# 1dpong.net
KiCad netlist of a schematic drawn in EAGLE
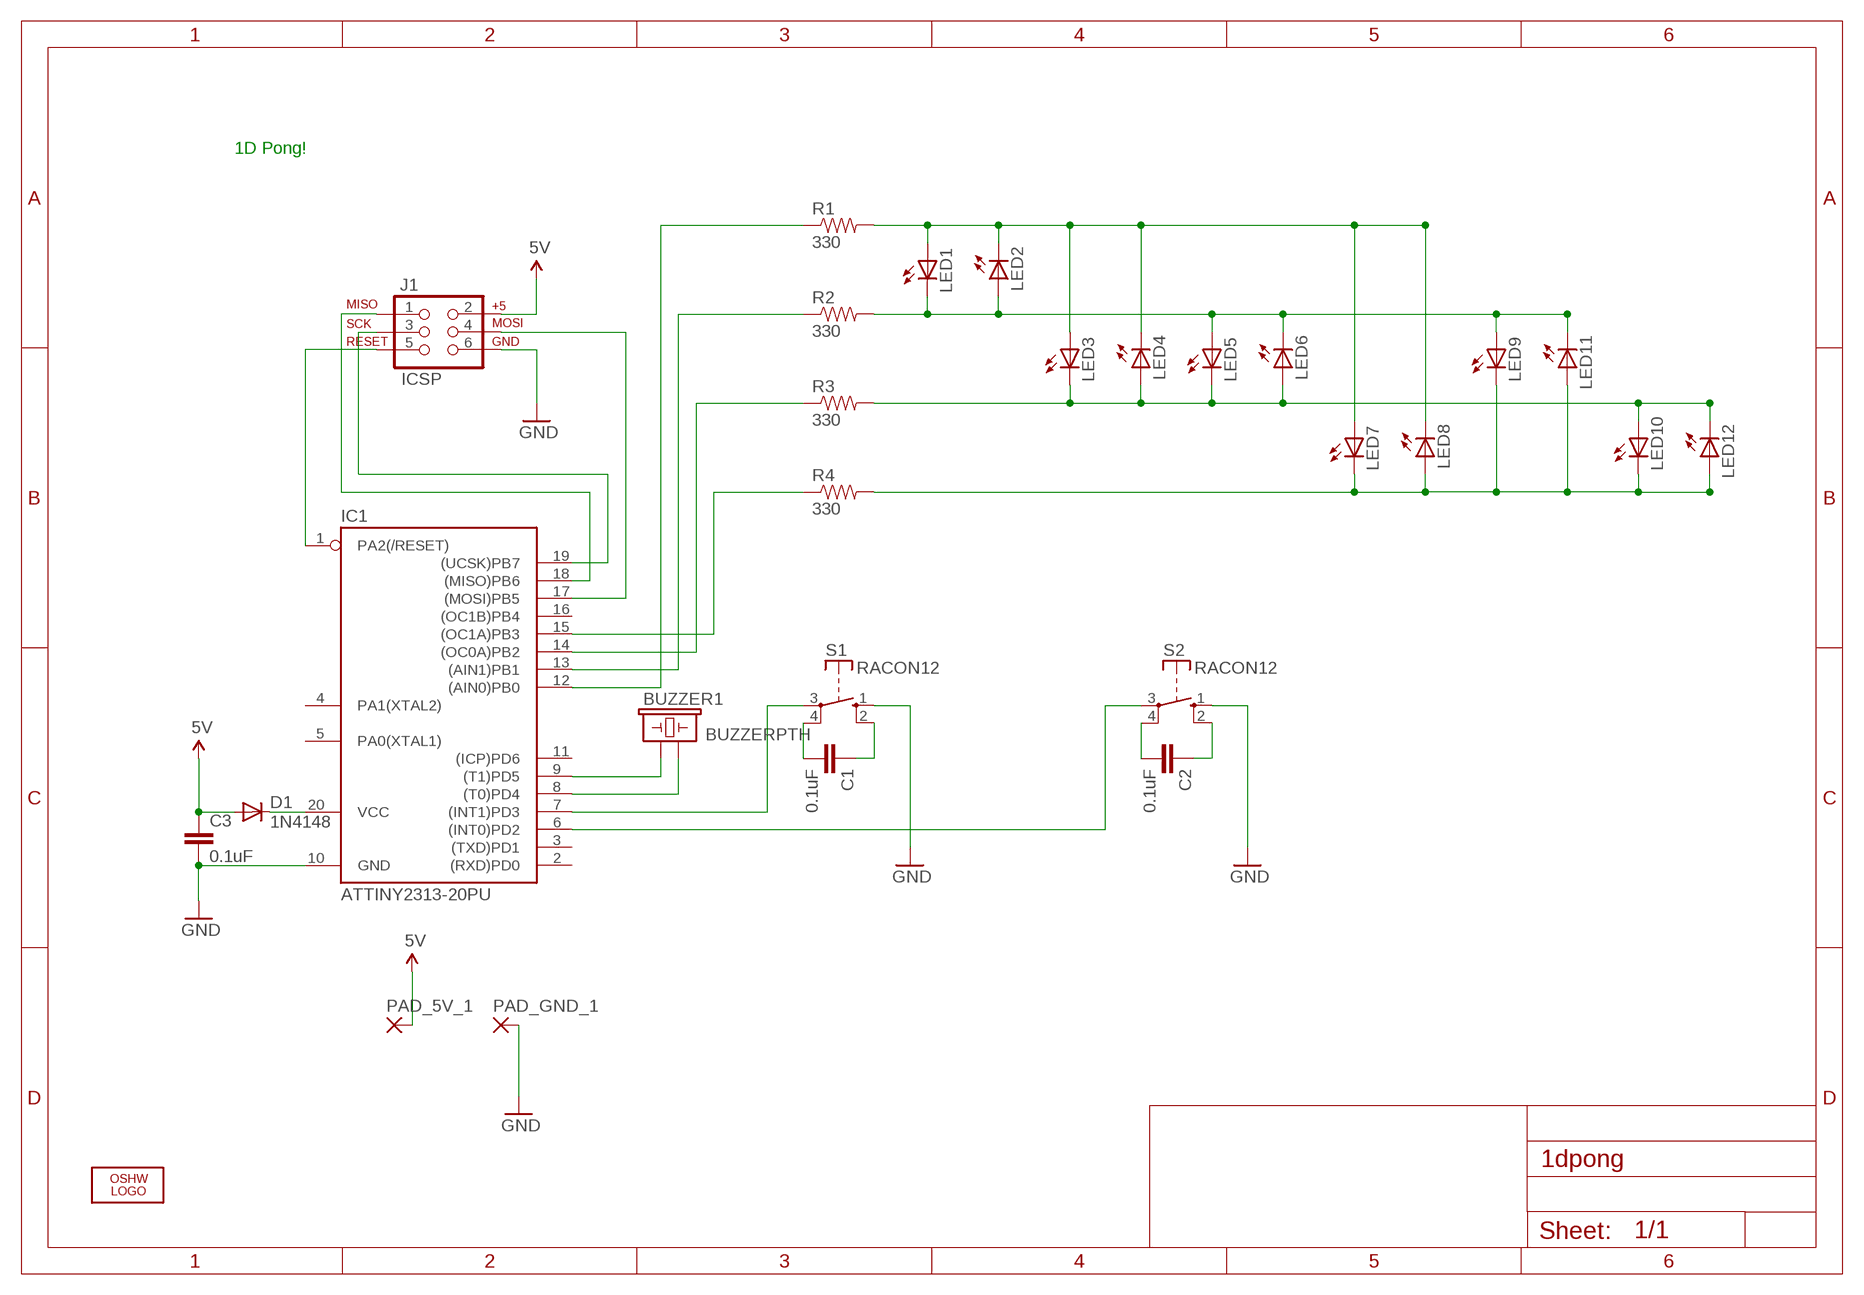
[diagram p0: schematic, sheet 1]

(export (version "E")
  (design (tool "Eeschema 10.0.6"))
  (components
    (comp (ref "BUZZER1")
      (value "BUZZERPTH")
      (footprint "eagle-import:BUZZER-12MM")
      (libsource (lib "eagle-import") (part "BUZZERPTH"))
    )
    (comp (ref "C1")
      (value "0.1uF")
      (footprint "eagle-import:CAP-PTH-SMALL")
      (libsource (lib "eagle-import") (part "CAPPTH"))
    )
    (comp (ref "C2")
      (value "0.1uF")
      (footprint "eagle-import:CAP-PTH-SMALL")
      (libsource (lib "eagle-import") (part "CAPPTH"))
    )
    (comp (ref "C3")
      (value "0.1uF")
      (footprint "eagle-import:CAP-PTH-SMALL")
      (libsource (lib "eagle-import") (part "CAPPTH"))
    )
    (comp (ref "D1")
      (value "1N4148")
      (footprint "eagle-import:DIODE-1N4148")
      (libsource (lib "eagle-import") (part "DIODE1N4148"))
    )
    (comp (ref "IC1")
      (value "ATTINY2313-20PU")
      (footprint "eagle-import:DIL20")
      (libsource (lib "eagle-import") (part "TINY2313-P"))
    )
    (comp (ref "J1")
      (value "ICSP")
      (footprint "eagle-import:2X3")
      (libsource (lib "eagle-import") (part "AVR_SPI_PRG_6PTH"))
    )
    (comp (ref "LED1")
      (value "LED5MM")
      (footprint "eagle-import:LED5MM")
      (libsource (lib "eagle-import") (part "LED5MM"))
    )
    (comp (ref "LED2")
      (value "LED5MM")
      (footprint "eagle-import:LED5MM")
      (libsource (lib "eagle-import") (part "LED5MM"))
    )
    (comp (ref "LED3")
      (value "LED5MM")
      (footprint "eagle-import:LED5MM")
      (libsource (lib "eagle-import") (part "LED5MM"))
    )
    (comp (ref "LED4")
      (value "LED5MM")
      (footprint "eagle-import:LED5MM")
      (libsource (lib "eagle-import") (part "LED5MM"))
    )
    (comp (ref "LED5")
      (value "LED5MM")
      (footprint "eagle-import:LED5MM")
      (libsource (lib "eagle-import") (part "LED5MM"))
    )
    (comp (ref "LED6")
      (value "LED5MM")
      (footprint "eagle-import:LED5MM")
      (libsource (lib "eagle-import") (part "LED5MM"))
    )
    (comp (ref "LED7")
      (value "LED5MM")
      (footprint "eagle-import:LED5MM")
      (libsource (lib "eagle-import") (part "LED5MM"))
    )
    (comp (ref "LED8")
      (value "LED5MM")
      (footprint "eagle-import:LED5MM")
      (libsource (lib "eagle-import") (part "LED5MM"))
    )
    (comp (ref "LED9")
      (value "LED5MM")
      (footprint "eagle-import:LED5MM")
      (libsource (lib "eagle-import") (part "LED5MM"))
    )
    (comp (ref "LED10")
      (value "LED5MM")
      (footprint "eagle-import:LED5MM")
      (libsource (lib "eagle-import") (part "LED5MM"))
    )
    (comp (ref "LED11")
      (value "LED5MM")
      (footprint "eagle-import:LED5MM")
      (libsource (lib "eagle-import") (part "LED5MM"))
    )
    (comp (ref "LED12")
      (value "LED5MM")
      (footprint "eagle-import:LED5MM")
      (libsource (lib "eagle-import") (part "LED5MM"))
    )
    (comp (ref "LOGO1")
      (value "OSHW_LOGO_FILLX0150-NT")
      (footprint "eagle-import:OSHW_FILLX150_NOTEXT")
      (libsource (lib "eagle-import") (part "OSHW_LOGO_FILLX0150-NT"))
    )
    (comp (ref "PAD_5V_1")
      (value "WIREPAD1,6/0,9")
      (footprint "eagle-import:1,6_0,9")
      (libsource (lib "eagle-import") (part "WIREPAD1,6/0,9"))
    )
    (comp (ref "PAD_GND_1")
      (value "WIREPAD1,6/0,9")
      (footprint "eagle-import:1,6_0,9")
      (libsource (lib "eagle-import") (part "WIREPAD1,6/0,9"))
    )
    (comp (ref "R1")
      (value "330")
      (footprint "eagle-import:AXIAL-0.4")
      (libsource (lib "eagle-import") (part "RESISTORPTH-1/4W"))
    )
    (comp (ref "R2")
      (value "330")
      (footprint "eagle-import:AXIAL-0.4")
      (libsource (lib "eagle-import") (part "RESISTORPTH-1/4W"))
    )
    (comp (ref "R3")
      (value "330")
      (footprint "eagle-import:AXIAL-0.4")
      (libsource (lib "eagle-import") (part "RESISTORPTH-1/4W"))
    )
    (comp (ref "R4")
      (value "330")
      (footprint "eagle-import:AXIAL-0.4")
      (libsource (lib "eagle-import") (part "RESISTORPTH-1/4W"))
    )
    (comp (ref "S1")
      (value "RACON12")
      (footprint "eagle-import:RACON12")
      (libsource (lib "eagle-import") (part "RACON12"))
    )
    (comp (ref "S2")
      (value "RACON12")
      (footprint "eagle-import:RACON12")
      (libsource (lib "eagle-import") (part "RACON12"))
    )
  )
  (nets
    (net (code "1") (name "5V") (class "Default")
      (node (ref "C3") (pin "1") (pinfunction "1_1") (pintype "passive"))
      (node (ref "D1") (pin "A") (pinfunction "A_A") (pintype "passive"))
      (node (ref "J1") (pin "2") (pinfunction "2_2") (pintype "passive"))
      (node (ref "PAD_5V_1") (pin "1") (pinfunction "P_1") (pintype "passive"))
    )
    (net (code "2") (name "GND") (class "Default")
      (node (ref "C3") (pin "2") (pinfunction "2_2") (pintype "passive"))
      (node (ref "IC1") (pin "10") (pinfunction "GND_10") (pintype "power_in"))
      (node (ref "J1") (pin "6") (pinfunction "6_6") (pintype "passive"))
      (node (ref "PAD_GND_1") (pin "1") (pinfunction "P_1") (pintype "passive"))
      (node (ref "S1") (pin "1") (pinfunction "S_1") (pintype "passive"))
      (node (ref "S2") (pin "1") (pinfunction "S_1") (pintype "passive"))
    )
    (net (code "3") (name "Net-(BUZZER1-1)") (class "Default")
      (node (ref "BUZZER1") (pin "+") (pinfunction "1_+") (pintype "passive"))
      (node (ref "IC1") (pin "9") (pinfunction "(T1)PD5_9") (pintype "bidirectional"))
    )
    (net (code "4") (name "Net-(BUZZER1-2)") (class "Default")
      (node (ref "BUZZER1") (pin "-") (pinfunction "2_-") (pintype "passive"))
      (node (ref "IC1") (pin "8") (pinfunction "(T0)PD4_8") (pintype "bidirectional"))
    )
    (net (code "5") (name "Net-(C1-Pad1)") (class "Default")
      (node (ref "C1") (pin "1") (pinfunction "1_1") (pintype "passive"))
      (node (ref "S1") (pin "2") (pinfunction "S_2") (pintype "passive"))
    )
    (net (code "6") (name "Net-(C1-Pad2)") (class "Default")
      (node (ref "C1") (pin "2") (pinfunction "2_2") (pintype "passive"))
      (node (ref "S1") (pin "4") (pinfunction "P_4") (pintype "passive"))
    )
    (net (code "7") (name "Net-(C2-Pad1)") (class "Default")
      (node (ref "C2") (pin "1") (pinfunction "1_1") (pintype "passive"))
      (node (ref "S2") (pin "2") (pinfunction "S_2") (pintype "passive"))
    )
    (net (code "8") (name "Net-(C2-Pad2)") (class "Default")
      (node (ref "C2") (pin "2") (pinfunction "2_2") (pintype "passive"))
      (node (ref "S2") (pin "4") (pinfunction "P_4") (pintype "passive"))
    )
    (net (code "9") (name "Net-(IC1-(AIN0)PB0)") (class "Default")
      (node (ref "IC1") (pin "12") (pinfunction "(AIN0)PB0_12") (pintype "bidirectional"))
      (node (ref "R1") (pin "P$1") (pinfunction "1_P$1") (pintype "passive"))
    )
    (net (code "10") (name "Net-(IC1-(AIN1)PB1)") (class "Default")
      (node (ref "IC1") (pin "13") (pinfunction "(AIN1)PB1_13") (pintype "bidirectional"))
      (node (ref "R2") (pin "P$1") (pinfunction "1_P$1") (pintype "passive"))
    )
    (net (code "11") (name "Net-(IC1-(INT0)PD2)") (class "Default")
      (node (ref "IC1") (pin "6") (pinfunction "(INT0)PD2_6") (pintype "bidirectional"))
      (node (ref "S2") (pin "3") (pinfunction "P_3") (pintype "passive"))
    )
    (net (code "12") (name "Net-(IC1-(INT1)PD3)") (class "Default")
      (node (ref "IC1") (pin "7") (pinfunction "(INT1)PD3_7") (pintype "bidirectional"))
      (node (ref "S1") (pin "3") (pinfunction "P_3") (pintype "passive"))
    )
    (net (code "13") (name "Net-(IC1-(MISO)PB6)") (class "Default")
      (node (ref "IC1") (pin "18") (pinfunction "(MISO)PB6_18") (pintype "bidirectional"))
      (node (ref "J1") (pin "1") (pinfunction "1_1") (pintype "passive"))
    )
    (net (code "14") (name "Net-(IC1-(MOSI)PB5)") (class "Default")
      (node (ref "IC1") (pin "17") (pinfunction "(MOSI)PB5_17") (pintype "bidirectional"))
      (node (ref "J1") (pin "4") (pinfunction "4_4") (pintype "passive"))
    )
    (net (code "15") (name "Net-(IC1-(OC0A)PB2)") (class "Default")
      (node (ref "IC1") (pin "14") (pinfunction "(OC0A)PB2_14") (pintype "bidirectional"))
      (node (ref "R3") (pin "P$1") (pinfunction "1_P$1") (pintype "passive"))
    )
    (net (code "16") (name "Net-(IC1-(OC1A)PB3)") (class "Default")
      (node (ref "IC1") (pin "15") (pinfunction "(OC1A)PB3_15") (pintype "bidirectional"))
      (node (ref "R4") (pin "P$1") (pinfunction "1_P$1") (pintype "passive"))
    )
    (net (code "17") (name "Net-(IC1-(UCSK)PB7)") (class "Default")
      (node (ref "IC1") (pin "19") (pinfunction "(UCSK)PB7_19") (pintype "bidirectional"))
      (node (ref "J1") (pin "3") (pinfunction "3_3") (pintype "passive"))
    )
    (net (code "18") (name "Net-(IC1-PA2({slash}RESET))") (class "Default")
      (node (ref "IC1") (pin "1") (pinfunction "PA2(/RESET)_1") (pintype "input"))
      (node (ref "J1") (pin "5") (pinfunction "5_5") (pintype "passive"))
    )
    (net (code "19") (name "Net-(IC1-VCC)") (class "Default")
      (node (ref "D1") (pin "C") (pinfunction "C_C") (pintype "passive"))
      (node (ref "IC1") (pin "20") (pinfunction "VCC_20") (pintype "power_in"))
    )
    (net (code "20") (name "Net-(LED1-C)") (class "Default")
      (node (ref "LED1") (pin "K") (pinfunction "C_K") (pintype "passive"))
      (node (ref "LED11") (pin "K") (pinfunction "C_K") (pintype "passive"))
      (node (ref "LED2") (pin "A") (pinfunction "A_A") (pintype "passive"))
      (node (ref "LED5") (pin "A") (pinfunction "A_A") (pintype "passive"))
      (node (ref "LED6") (pin "K") (pinfunction "C_K") (pintype "passive"))
      (node (ref "LED9") (pin "A") (pinfunction "A_A") (pintype "passive"))
      (node (ref "R2") (pin "P$2") (pinfunction "2_P$2") (pintype "passive"))
    )
    (net (code "21") (name "Net-(LED2-C)") (class "Default")
      (node (ref "LED1") (pin "A") (pinfunction "A_A") (pintype "passive"))
      (node (ref "LED2") (pin "K") (pinfunction "C_K") (pintype "passive"))
      (node (ref "LED3") (pin "A") (pinfunction "A_A") (pintype "passive"))
      (node (ref "LED4") (pin "K") (pinfunction "C_K") (pintype "passive"))
      (node (ref "LED7") (pin "A") (pinfunction "A_A") (pintype "passive"))
      (node (ref "LED8") (pin "K") (pinfunction "C_K") (pintype "passive"))
      (node (ref "R1") (pin "P$2") (pinfunction "2_P$2") (pintype "passive"))
    )
    (net (code "22") (name "Net-(LED10-C)") (class "Default")
      (node (ref "LED10") (pin "K") (pinfunction "C_K") (pintype "passive"))
      (node (ref "LED11") (pin "A") (pinfunction "A_A") (pintype "passive"))
      (node (ref "LED12") (pin "A") (pinfunction "A_A") (pintype "passive"))
      (node (ref "LED7") (pin "K") (pinfunction "C_K") (pintype "passive"))
      (node (ref "LED8") (pin "A") (pinfunction "A_A") (pintype "passive"))
      (node (ref "LED9") (pin "K") (pinfunction "C_K") (pintype "passive"))
      (node (ref "R4") (pin "P$2") (pinfunction "2_P$2") (pintype "passive"))
    )
    (net (code "23") (name "Net-(LED12-C)") (class "Default")
      (node (ref "LED10") (pin "A") (pinfunction "A_A") (pintype "passive"))
      (node (ref "LED12") (pin "K") (pinfunction "C_K") (pintype "passive"))
      (node (ref "LED3") (pin "K") (pinfunction "C_K") (pintype "passive"))
      (node (ref "LED4") (pin "A") (pinfunction "A_A") (pintype "passive"))
      (node (ref "LED5") (pin "K") (pinfunction "C_K") (pintype "passive"))
      (node (ref "LED6") (pin "A") (pinfunction "A_A") (pintype "passive"))
      (node (ref "R3") (pin "P$2") (pinfunction "2_P$2") (pintype "passive"))
    )
    (net (code "24") (name "unconnected-(IC1-(ICP)PD6-Pad11)") (class "Default")
      (node (ref "IC1") (pin "11") (pinfunction "(ICP)PD6_11") (pintype "bidirectional"))
    )
    (net (code "25") (name "unconnected-(IC1-(OC1B)PB4-Pad16)") (class "Default")
      (node (ref "IC1") (pin "16") (pinfunction "(OC1B)PB4_16") (pintype "bidirectional"))
    )
    (net (code "26") (name "unconnected-(IC1-(RXD)PD0-Pad2)") (class "Default")
      (node (ref "IC1") (pin "2") (pinfunction "(RXD)PD0_2") (pintype "bidirectional"))
    )
    (net (code "27") (name "unconnected-(IC1-(TXD)PD1-Pad3)") (class "Default")
      (node (ref "IC1") (pin "3") (pinfunction "(TXD)PD1_3") (pintype "bidirectional"))
    )
    (net (code "28") (name "unconnected-(IC1-PA0(XTAL1)-Pad5)") (class "Default")
      (node (ref "IC1") (pin "5") (pinfunction "PA0(XTAL1)_5") (pintype "bidirectional"))
    )
    (net (code "29") (name "unconnected-(IC1-PA1(XTAL2)-Pad4)") (class "Default")
      (node (ref "IC1") (pin "4") (pinfunction "PA1(XTAL2)_4") (pintype "bidirectional"))
    )
  )
)
